# RS485.net
KiCad netlist of a schematic drawn in Altium Designer
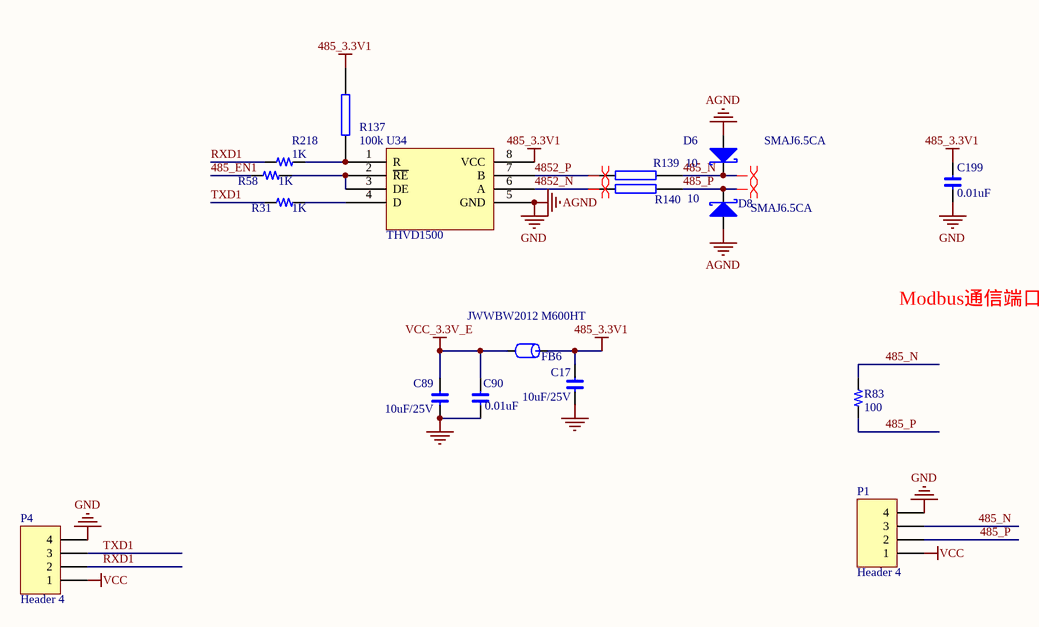
[diagram p0: RS485.SchDoc]

(export (version "E")
  (design (tool "Eeschema 10.0.6"))
  (components
    (comp (ref "C17")
      (value "10uF/25V")
      (footprint "0603C")
      (description "C")
      (libsource (lib "Schlib_20110825") (part "C"))
    )
    (comp (ref "C89")
      (value "10uF/25V")
      (footprint "0603C")
      (description "C")
      (libsource (lib "Schlib_20110825") (part "C"))
    )
    (comp (ref "C90")
      (value "0.01uF")
      (footprint "0603C")
      (description "C")
      (libsource (lib "Schlib_20110825") (part "C"))
    )
    (comp (ref "C199")
      (value "0.01uF")
      (footprint "0603C")
      (description "C")
      (libsource (lib "Schlib_20110825") (part "C"))
    )
    (comp (ref "D6")
      (value "SMAJ6.5CA")
      (footprint "SMA")
      (description "Schottky Diode")
      (libsource (lib "*") (part "DIODE S"))
    )
    (comp (ref "D8")
      (value "SMAJ6.5CA")
      (footprint "SMA")
      (description "Schottky Diode")
      (libsource (lib "*") (part "DIODE S"))
    )
    (comp (ref "FB6")
      (value "JWWBW2012 M600HT")
      (footprint "0805CZ")
      (libsource (lib "Schlib_20110825") (part "FB"))
    )
    (comp (ref "P1")
      (value "Header 4")
      (footprint "HDR1X4")
      (description "Header, 4-Pin")
      (fields (field (name "PUBLISHER") "Altium Limited"))
      (libsource (lib "Miscellaneous Connectors") (part "Header 4"))
    )
    (comp (ref "P4")
      (value "Header 4")
      (footprint "HDR1X4")
      (description "Header, 4-Pin")
      (fields (field (name "PUBLISHER") "Altium Limited"))
      (libsource (lib "Miscellaneous Connectors") (part "Header 4"))
    )
    (comp (ref "R31") (value "1K") (footprint "0603R") (description "R") (libsource (lib "JRJ_1") (part "R")))
    (comp (ref "R58") (value "1K") (footprint "0603R") (description "R") (libsource (lib "JRJ_1") (part "R")))
    (comp (ref "R83")
      (value "100")
      (footprint "0603R")
      (description "R")
      (libsource (lib "JRJ_1") (part "R"))
    )
    (comp (ref "R137") (value "100k") (footprint "0603R") (libsource (lib "*") (part "RES2")))
    (comp (ref "R139") (value "10") (footprint "1206R") (libsource (lib "*") (part "RES2")))
    (comp (ref "R140") (value "10") (footprint "1206R") (libsource (lib "*") (part "RES2")))
    (comp (ref "R218")
      (value "1K")
      (footprint "0603R")
      (description "R")
      (libsource (lib "JRJ_1") (part "R"))
    )
    (comp (ref "U34") (value "THVD1500") (footprint "so-8") (libsource (lib "Schlib1") (part "SN65HVD06D")))
  )
  (nets
    (net (code "1") (name "/485_EN1") (class "Default") (node (ref "R58") (pin "2") (pintype "passive")))
    (net (code "2") (name "/485_N") (class "Default")
      (node (ref "D6") (pin "2") (pinfunction "K_2") (pintype "passive"))
      (node (ref "P1") (pin "3") (pinfunction "3_3") (pintype "passive"))
      (node (ref "R139") (pin "1") (pinfunction "1_1") (pintype "passive"))
      (node (ref "R83") (pin "2") (pintype "passive"))
    )
    (net (code "3") (name "/485_P") (class "Default")
      (node (ref "D8") (pin "2") (pinfunction "K_2") (pintype "passive"))
      (node (ref "P1") (pin "2") (pinfunction "2_2") (pintype "passive"))
      (node (ref "R140") (pin "1") (pinfunction "1_1") (pintype "passive"))
      (node (ref "R83") (pin "1") (pintype "passive"))
    )
    (net (code "4") (name "/4852_N") (class "Default")
      (node (ref "R140") (pin "2") (pinfunction "2_2") (pintype "passive"))
      (node (ref "U34") (pin "6") (pinfunction "A_6") (pintype "passive"))
    )
    (net (code "5") (name "/4852_P") (class "Default")
      (node (ref "R139") (pin "2") (pinfunction "2_2") (pintype "passive"))
      (node (ref "U34") (pin "7") (pinfunction "B_7") (pintype "passive"))
    )
    (net (code "6") (name "/RXD1") (class "Default")
      (node (ref "P4") (pin "2") (pinfunction "2_2") (pintype "passive"))
      (node (ref "R218") (pin "2") (pintype "passive"))
    )
    (net (code "7") (name "/TXD1") (class "Default")
      (node (ref "P4") (pin "3") (pinfunction "3_3") (pintype "passive"))
      (node (ref "R31") (pin "2") (pintype "passive"))
    )
    (net (code "8") (name "485_3.3V1") (class "Default")
      (node (ref "C17") (pin "2") (pintype "passive"))
      (node (ref "C199") (pin "2") (pintype "passive"))
      (node (ref "FB6") (pin "1") (pintype "passive"))
      (node (ref "R137") (pin "2") (pinfunction "2_2") (pintype "passive"))
      (node (ref "U34") (pin "8") (pinfunction "VCC_8") (pintype "passive"))
    )
    (net (code "9") (name "AGND") (class "Default")
      (node (ref "C17") (pin "1") (pintype "passive"))
      (node (ref "C199") (pin "1") (pintype "passive"))
      (node (ref "C89") (pin "1") (pintype "passive"))
      (node (ref "C90") (pin "1") (pintype "passive"))
      (node (ref "D6") (pin "1") (pinfunction "A_1") (pintype "passive"))
      (node (ref "D8") (pin "1") (pinfunction "A_1") (pintype "passive"))
      (node (ref "P1") (pin "4") (pinfunction "4_4") (pintype "passive"))
      (node (ref "P4") (pin "4") (pinfunction "4_4") (pintype "passive"))
      (node (ref "U34") (pin "5") (pinfunction "GND_5") (pintype "passive"))
    )
    (net (code "10") (name "Net-(U34-D)") (class "Default")
      (node (ref "R31") (pin "1") (pintype "passive"))
      (node (ref "U34") (pin "4") (pinfunction "D_4") (pintype "passive"))
    )
    (net (code "11") (name "Net-(U34-DE)") (class "Default")
      (node (ref "R58") (pin "1") (pintype "passive"))
      (node (ref "U34") (pin "2") (pinfunction "~{RE}_2") (pintype "passive"))
      (node (ref "U34") (pin "3") (pinfunction "DE_3") (pintype "passive"))
    )
    (net (code "12") (name "Net-(U34-R)") (class "Default")
      (node (ref "R137") (pin "1") (pinfunction "1_1") (pintype "passive"))
      (node (ref "R218") (pin "1") (pintype "passive"))
      (node (ref "U34") (pin "1") (pinfunction "R_1") (pintype "passive"))
    )
    (net (code "13") (name "VCC") (class "Default")
      (node (ref "P1") (pin "1") (pinfunction "1_1") (pintype "passive"))
      (node (ref "P4") (pin "1") (pinfunction "1_1") (pintype "passive"))
    )
    (net (code "14") (name "VCC_3.3V_E") (class "Default")
      (node (ref "C89") (pin "2") (pintype "passive"))
      (node (ref "C90") (pin "2") (pintype "passive"))
      (node (ref "FB6") (pin "2") (pintype "passive"))
    )
  )
)
